# MPU.net
KiCad netlist of a schematic drawn in EAGLE
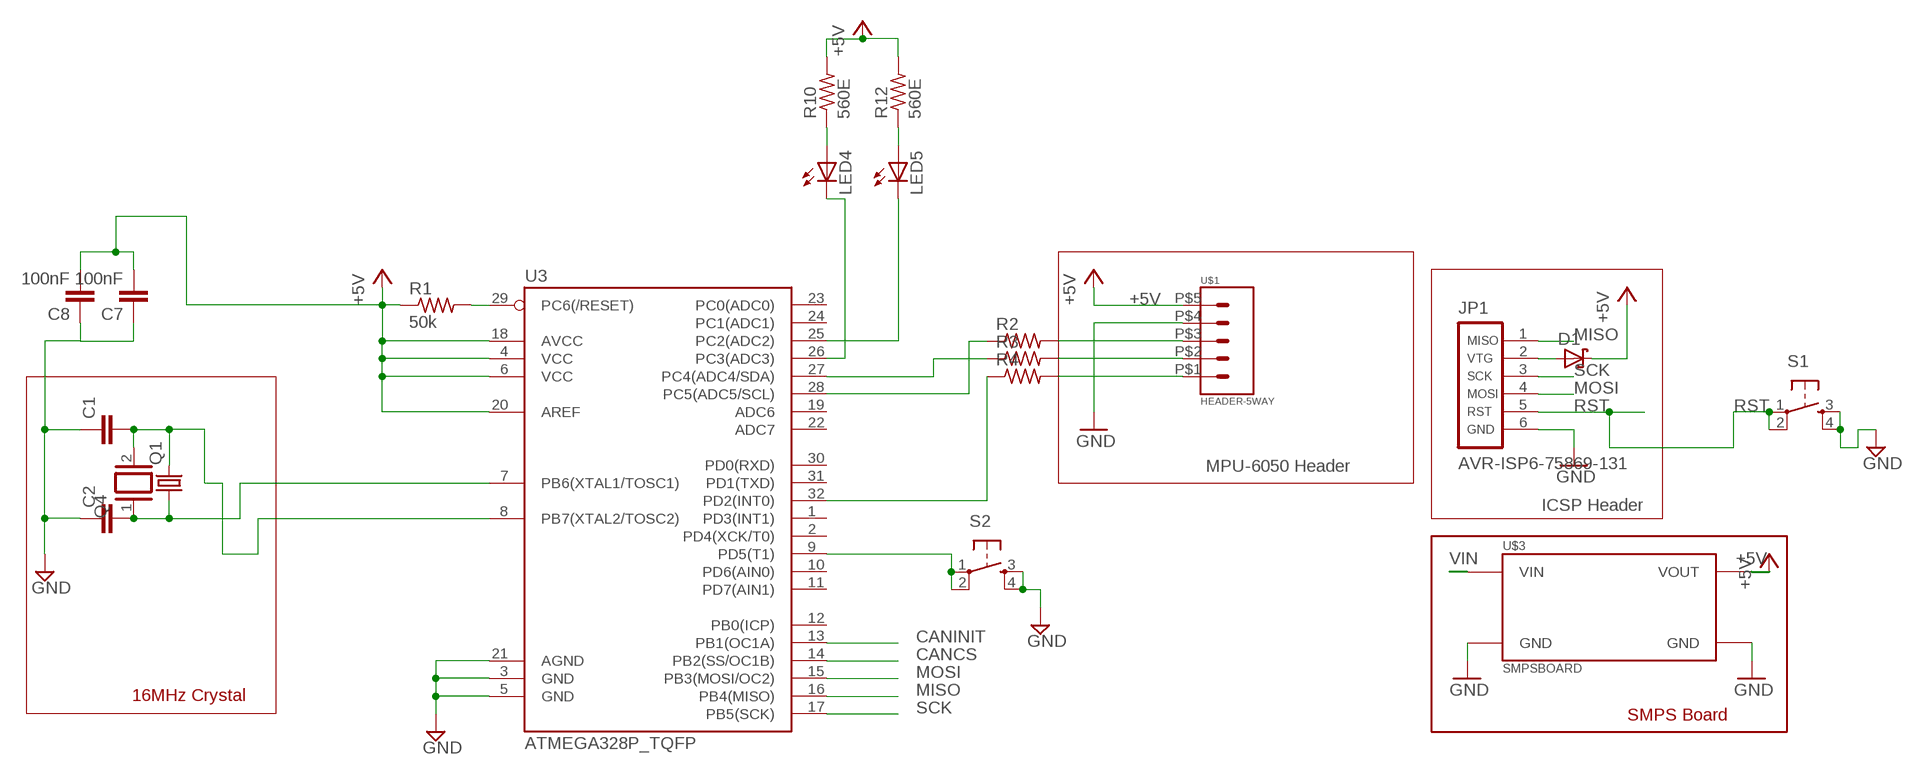
[diagram p0: schematic, sheet 1]
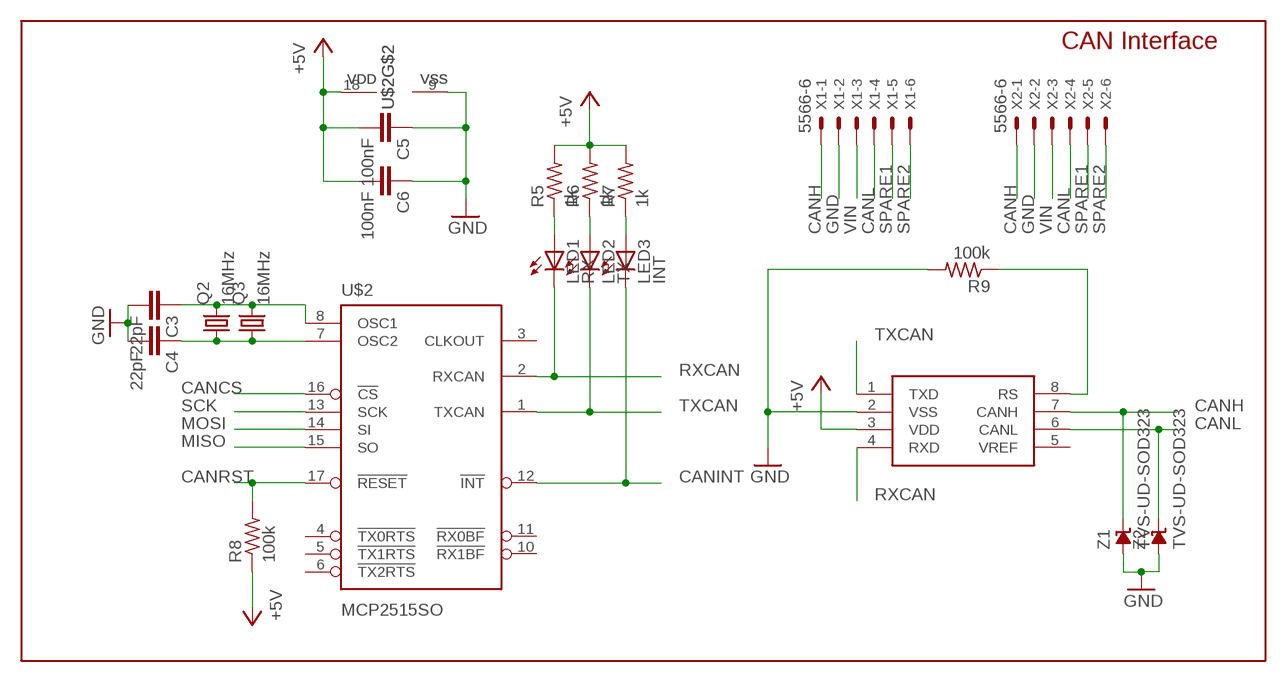
[diagram p1: schematic, sheet 2]

(export (version "E")
  (design (tool "Eeschema 10.0.6"))
  (components
    (comp (ref "C3")
      (value "22pF")
      (footprint "eagle-import:C0805K")
      (libsource (lib "eagle-import") (part "C-EUC0805K"))
    )
    (comp (ref "C4")
      (value "22pF")
      (footprint "eagle-import:C0805K")
      (libsource (lib "eagle-import") (part "C-EUC0805K"))
    )
    (comp (ref "C5")
      (value "100nF")
      (footprint "eagle-import:C0805K")
      (libsource (lib "eagle-import") (part "C-EUC0805K"))
    )
    (comp (ref "C6")
      (value "100nF")
      (footprint "eagle-import:C0805K")
      (libsource (lib "eagle-import") (part "C-EUC0805K"))
    )
    (comp (ref "LED1")
      (value "RX")
      (footprint "eagle-import:CHIP-LED0805")
      (libsource (lib "eagle-import") (part "LEDCHIP-LED0805"))
    )
    (comp (ref "LED2")
      (value "TX")
      (footprint "eagle-import:CHIP-LED0805")
      (libsource (lib "eagle-import") (part "LEDCHIP-LED0805"))
    )
    (comp (ref "LED3")
      (value "INT")
      (footprint "eagle-import:CHIP-LED0805")
      (libsource (lib "eagle-import") (part "LEDCHIP-LED0805"))
    )
    (comp (ref "Q2")
      (value "16MHz")
      (footprint "eagle-import:HC49_S")
      (libsource (lib "eagle-import") (part "CRYSTALHC49S"))
    )
    (comp (ref "Q3")
      (value "16MHz")
      (footprint "eagle-import:HC49UP")
      (libsource (lib "eagle-import") (part "CRYSTALHC49UP"))
    )
    (comp (ref "R5")
      (value "1k")
      (footprint "eagle-import:R0805")
      (libsource (lib "eagle-import") (part "R-US_R0805"))
    )
    (comp (ref "R6")
      (value "1k")
      (footprint "eagle-import:R0805")
      (libsource (lib "eagle-import") (part "R-US_R0805"))
    )
    (comp (ref "R7")
      (value "1k")
      (footprint "eagle-import:R0805")
      (libsource (lib "eagle-import") (part "R-US_R0805"))
    )
    (comp (ref "R8")
      (value "100k")
      (footprint "eagle-import:R0805")
      (libsource (lib "eagle-import") (part "R-US_R0805"))
    )
    (comp (ref "R9")
      (value "100k")
      (footprint "eagle-import:R0805")
      (libsource (lib "eagle-import") (part "R-US_R0805"))
    )
    (comp (ref "U$2")
      (value "MCP2515SO")
      (footprint "eagle-import:SO-18W")
      (libsource (lib "eagle-import") (part "MCP2515SO"))
    )
    (comp (ref "U2")
      (value "MCP2551")
      (footprint "eagle-import:SO08")
      (libsource (lib "eagle-import") (part "MCP2551"))
    )
    (comp (ref "X1")
      (value "5566-6")
      (footprint "eagle-import:5566-6")
      (fields (field (name "MPN") "95566-61002"))
      (libsource (lib "eagle-import") (part "5566-6"))
    )
    (comp (ref "X2")
      (value "5566-6")
      (footprint "eagle-import:5566-6")
      (fields (field (name "MPN") "95566-61002"))
      (libsource (lib "eagle-import") (part "5566-6"))
    )
    (comp (ref "Z1")
      (value "TVS-UD-SOD323")
      (footprint "eagle-import:SOD323")
      (libsource (lib "eagle-import") (part "TVS-UD-SOD323"))
    )
    (comp (ref "Z2")
      (value "TVS-UD-SOD323")
      (footprint "eagle-import:SOD323")
      (libsource (lib "eagle-import") (part "TVS-UD-SOD323"))
    )
    (comp (ref "C1")
      (value "C-EUC0805")
      (footprint "eagle-import:C0805")
      (libsource (lib "eagle-import") (part "C-EUC0805"))
    )
    (comp (ref "C2")
      (value "C-EUC0805")
      (footprint "eagle-import:C0805")
      (libsource (lib "eagle-import") (part "C-EUC0805"))
    )
    (comp (ref "C7")
      (value "100nF")
      (footprint "eagle-import:C0805")
      (libsource (lib "eagle-import") (part "C-EUC0805"))
    )
    (comp (ref "C8")
      (value "100nF")
      (footprint "eagle-import:C0805")
      (libsource (lib "eagle-import") (part "C-EUC0805"))
    )
    (comp (ref "D1")
      (value "SCHOTTKY-DIODESMD")
      (footprint "eagle-import:SMB")
      (libsource (lib "eagle-import") (part "SCHOTTKY-DIODESMD"))
    )
    (comp (ref "JP1")
      (value "AVR-ISP6-75869-131")
      (footprint "eagle-import:HDR-75869-131")
      (libsource (lib "eagle-import") (part "AVR-ISP6-75869-131"))
    )
    (comp (ref "LED4")
      (value "LEDCHIP-LED0805")
      (footprint "eagle-import:CHIP-LED0805")
      (libsource (lib "eagle-import") (part "LEDCHIP-LED0805"))
    )
    (comp (ref "LED5")
      (value "LEDCHIP-LED0805")
      (footprint "eagle-import:CHIP-LED0805")
      (libsource (lib "eagle-import") (part "LEDCHIP-LED0805"))
    )
    (comp (ref "Q1")
      (value "CRYSTALHC49UP")
      (footprint "eagle-import:HC49UP")
      (libsource (lib "eagle-import") (part "CRYSTALHC49UP"))
    )
    (comp (ref "Q4")
      (value "XTAL/S")
      (footprint "eagle-import:QS")
      (libsource (lib "eagle-import") (part "XTAL/S"))
    )
    (comp (ref "R1")
      (value "50k")
      (footprint "eagle-import:M0805")
      (libsource (lib "eagle-import") (part "R-US_M0805"))
    )
    (comp (ref "R2")
      (value "R-US_M0805")
      (footprint "eagle-import:M0805")
      (libsource (lib "eagle-import") (part "R-US_M0805"))
    )
    (comp (ref "R3")
      (value "R-US_M0805")
      (footprint "eagle-import:M0805")
      (libsource (lib "eagle-import") (part "R-US_M0805"))
    )
    (comp (ref "R4")
      (value "R-US_M0805")
      (footprint "eagle-import:M0805")
      (libsource (lib "eagle-import") (part "R-US_M0805"))
    )
    (comp (ref "R10")
      (value "560E")
      (footprint "eagle-import:M0805")
      (libsource (lib "eagle-import") (part "R-US_M0805"))
    )
    (comp (ref "R12")
      (value "560E")
      (footprint "eagle-import:M0805")
      (libsource (lib "eagle-import") (part "R-US_M0805"))
    )
    (comp (ref "S1")
      (value "TAC_SWITCHSMD")
      (footprint "eagle-import:TACTILE_SWITCH_SMD")
      (libsource (lib "eagle-import") (part "TAC_SWITCHSMD"))
    )
    (comp (ref "S2")
      (value "TAC_SWITCHSMD")
      (footprint "eagle-import:TACTILE_SWITCH_SMD")
      (libsource (lib "eagle-import") (part "TAC_SWITCHSMD"))
    )
    (comp (ref "U$1")
      (value "HEADER-5WAY")
      (footprint "eagle-import:1744426-5")
      (libsource (lib "eagle-import") (part "HEADER-5WAY"))
    )
    (comp (ref "U$3")
      (value "SMPSBOARD")
      (footprint "eagle-import:SMPSBOARD")
      (libsource (lib "eagle-import") (part "SMPSBOARD"))
    )
    (comp (ref "U3")
      (value "ATMEGA328P_TQFP")
      (footprint "eagle-import:TQFP32-08")
      (libsource (lib "eagle-import") (part "ATMEGA328P_TQFP"))
    )
  )
  (nets
    (net (code "1") (name "+5V") (class "Default")
      (node (ref "C5") (pin "2") (pinfunction "2_2") (pintype "passive"))
      (node (ref "C6") (pin "2") (pinfunction "2_2") (pintype "passive"))
      (node (ref "C7") (pin "2") (pinfunction "2_2") (pintype "passive"))
      (node (ref "C8") (pin "2") (pinfunction "2_2") (pintype "passive"))
      (node (ref "D1") (pin "C") (pinfunction "C_C") (pintype "passive"))
      (node (ref "R1") (pin "1") (pinfunction "1_1") (pintype "passive"))
      (node (ref "R10") (pin "2") (pinfunction "2_2") (pintype "passive"))
      (node (ref "R12") (pin "2") (pinfunction "2_2") (pintype "passive"))
      (node (ref "R5") (pin "2") (pinfunction "2_2") (pintype "passive"))
      (node (ref "R6") (pin "2") (pinfunction "2_2") (pintype "passive"))
      (node (ref "R7") (pin "2") (pinfunction "2_2") (pintype "passive"))
      (node (ref "R8") (pin "1") (pinfunction "1_1") (pintype "passive"))
      (node (ref "U$1") (pin "P$5") (pinfunction "P$5_P$5") (pintype "passive"))
      (node (ref "U$2") (pin "18") (pinfunction "VDD_18") (pintype "power_in"))
      (node (ref "U$3") (pin "VOUT") (pinfunction "VOUT_VOUT") (pintype "bidirectional"))
      (node (ref "U2") (pin "3") (pinfunction "VDD_3") (pintype "bidirectional"))
      (node (ref "U3") (pin "18") (pinfunction "AVCC_18") (pintype "bidirectional"))
      (node (ref "U3") (pin "20") (pinfunction "AREF_20") (pintype "bidirectional"))
      (node (ref "U3") (pin "4") (pinfunction "VCC_4") (pintype "bidirectional"))
      (node (ref "U3") (pin "6") (pinfunction "VCC_6") (pintype "bidirectional"))
    )
    (net (code "2") (name "CANCS") (class "Default")
      (node (ref "U$2") (pin "16") (pinfunction "~{CS}_16") (pintype "input"))
      (node (ref "U3") (pin "14") (pinfunction "PB2(SS/OC1B)_14") (pintype "bidirectional"))
    )
    (net (code "3") (name "CANH") (class "Default")
      (node (ref "U2") (pin "7") (pinfunction "CANH_7") (pintype "bidirectional"))
      (node (ref "X1") (pin "1") (pinfunction "S_1") (pintype "passive"))
      (node (ref "X2") (pin "1") (pinfunction "S_1") (pintype "passive"))
      (node (ref "Z1") (pin "C") (pinfunction "C_C") (pintype "passive"))
    )
    (net (code "4") (name "CANINIT") (class "Default")
      (node (ref "U3") (pin "13") (pinfunction "PB1(OC1A)_13") (pintype "bidirectional"))
    )
    (net (code "5") (name "CANINT") (class "Default")
      (node (ref "LED3") (pin "C") (pinfunction "C_C") (pintype "passive"))
      (node (ref "U$2") (pin "12") (pinfunction "~{INT}_12") (pintype "output"))
    )
    (net (code "6") (name "CANL") (class "Default")
      (node (ref "U2") (pin "6") (pinfunction "CANL_6") (pintype "bidirectional"))
      (node (ref "X1") (pin "4") (pinfunction "S_4") (pintype "passive"))
      (node (ref "X2") (pin "4") (pinfunction "S_4") (pintype "passive"))
      (node (ref "Z2") (pin "C") (pinfunction "C_C") (pintype "passive"))
    )
    (net (code "7") (name "CANRST") (class "Default")
      (node (ref "R8") (pin "2") (pinfunction "2_2") (pintype "passive"))
      (node (ref "U$2") (pin "17") (pinfunction "~{RESET}_17") (pintype "input"))
    )
    (net (code "8") (name "GND") (class "Default")
      (node (ref "C1") (pin "1") (pinfunction "1_1") (pintype "passive"))
      (node (ref "C2") (pin "1") (pinfunction "1_1") (pintype "passive"))
      (node (ref "C3") (pin "2") (pinfunction "2_2") (pintype "passive"))
      (node (ref "C4") (pin "2") (pinfunction "2_2") (pintype "passive"))
      (node (ref "C5") (pin "1") (pinfunction "1_1") (pintype "passive"))
      (node (ref "C6") (pin "1") (pinfunction "1_1") (pintype "passive"))
      (node (ref "C7") (pin "1") (pinfunction "1_1") (pintype "passive"))
      (node (ref "C8") (pin "1") (pinfunction "1_1") (pintype "passive"))
      (node (ref "JP1") (pin "6") (pinfunction "6_6") (pintype "passive"))
      (node (ref "R9") (pin "2") (pinfunction "2_2") (pintype "passive"))
      (node (ref "S1") (pin "3") (pinfunction "3_3") (pintype "passive"))
      (node (ref "S1") (pin "4") (pinfunction "4_4") (pintype "passive"))
      (node (ref "S2") (pin "3") (pinfunction "3_3") (pintype "passive"))
      (node (ref "S2") (pin "4") (pinfunction "4_4") (pintype "passive"))
      (node (ref "U$1") (pin "P$4") (pinfunction "P$4_P$4") (pintype "passive"))
      (node (ref "U$2") (pin "9") (pinfunction "VSS_9") (pintype "power_in"))
      (node (ref "U$3") (pin "GND") (pinfunction "GND_GND") (pintype "bidirectional"))
      (node (ref "U$3") (pin "GND@") (pinfunction "GND_GND@") (pintype "bidirectional"))
      (node (ref "U2") (pin "2") (pinfunction "VSS_2") (pintype "bidirectional"))
      (node (ref "U3") (pin "21") (pinfunction "AGND_21") (pintype "bidirectional"))
      (node (ref "U3") (pin "3") (pinfunction "GND_3") (pintype "bidirectional"))
      (node (ref "U3") (pin "5") (pinfunction "GND_5") (pintype "bidirectional"))
      (node (ref "X1") (pin "2") (pinfunction "S_2") (pintype "passive"))
      (node (ref "X2") (pin "2") (pinfunction "S_2") (pintype "passive"))
      (node (ref "Z1") (pin "A") (pinfunction "A_A") (pintype "passive"))
      (node (ref "Z2") (pin "A") (pinfunction "A_A") (pintype "passive"))
    )
    (net (code "9") (name "MISO") (class "Default")
      (node (ref "JP1") (pin "1") (pinfunction "1_1") (pintype "passive"))
      (node (ref "U$2") (pin "15") (pinfunction "SO_15") (pintype "output"))
      (node (ref "U3") (pin "16") (pinfunction "PB4(MISO)_16") (pintype "bidirectional"))
    )
    (net (code "10") (name "MOSI") (class "Default")
      (node (ref "JP1") (pin "4") (pinfunction "4_4") (pintype "passive"))
      (node (ref "U$2") (pin "14") (pinfunction "SI_14") (pintype "input"))
      (node (ref "U3") (pin "15") (pinfunction "PB3(MOSI/OC2)_15") (pintype "bidirectional"))
    )
    (net (code "11") (name "Net-(D1-PadA)") (class "Default")
      (node (ref "D1") (pin "A") (pinfunction "A_A") (pintype "passive"))
      (node (ref "JP1") (pin "2") (pinfunction "2_2") (pintype "passive"))
    )
    (net (code "12") (name "Net-(LED1-PadA)") (class "Default")
      (node (ref "LED1") (pin "A") (pinfunction "A_A") (pintype "passive"))
      (node (ref "R5") (pin "1") (pinfunction "1_1") (pintype "passive"))
    )
    (net (code "13") (name "Net-(LED2-PadA)") (class "Default")
      (node (ref "LED2") (pin "A") (pinfunction "A_A") (pintype "passive"))
      (node (ref "R6") (pin "1") (pinfunction "1_1") (pintype "passive"))
    )
    (net (code "14") (name "Net-(LED3-PadA)") (class "Default")
      (node (ref "LED3") (pin "A") (pinfunction "A_A") (pintype "passive"))
      (node (ref "R7") (pin "1") (pinfunction "1_1") (pintype "passive"))
    )
    (net (code "15") (name "Net-(LED4-PadA)") (class "Default")
      (node (ref "LED4") (pin "A") (pinfunction "A_A") (pintype "passive"))
      (node (ref "R10") (pin "1") (pinfunction "1_1") (pintype "passive"))
    )
    (net (code "16") (name "Net-(LED5-PadA)") (class "Default")
      (node (ref "LED5") (pin "A") (pinfunction "A_A") (pintype "passive"))
      (node (ref "R12") (pin "1") (pinfunction "1_1") (pintype "passive"))
    )
    (net (code "17") (name "Net-(R2-Pad2)") (class "Default")
      (node (ref "R2") (pin "2") (pinfunction "2_2") (pintype "passive"))
      (node (ref "U$1") (pin "P$3") (pinfunction "P$3_P$3") (pintype "passive"))
    )
    (net (code "18") (name "Net-(R3-Pad2)") (class "Default")
      (node (ref "R3") (pin "2") (pinfunction "2_2") (pintype "passive"))
      (node (ref "U$1") (pin "P$2") (pinfunction "P$2_P$2") (pintype "passive"))
    )
    (net (code "19") (name "Net-(R4-Pad2)") (class "Default")
      (node (ref "R4") (pin "2") (pinfunction "2_2") (pintype "passive"))
      (node (ref "U$1") (pin "P$1") (pinfunction "P$1_P$1") (pintype "passive"))
    )
    (net (code "20") (name "Net-(U$2A-OSC1)") (class "Default")
      (node (ref "C3") (pin "1") (pinfunction "1_1") (pintype "passive"))
      (node (ref "Q2") (pin "2") (pinfunction "2_2") (pintype "passive"))
      (node (ref "Q3") (pin "2") (pinfunction "2_2") (pintype "passive"))
      (node (ref "U$2") (pin "8") (pinfunction "OSC1_8") (pintype "input"))
    )
    (net (code "21") (name "Net-(U$2A-OSC2)") (class "Default")
      (node (ref "C4") (pin "1") (pinfunction "1_1") (pintype "passive"))
      (node (ref "Q2") (pin "1") (pinfunction "1_1") (pintype "passive"))
      (node (ref "Q3") (pin "1") (pinfunction "1_1") (pintype "passive"))
      (node (ref "U$2") (pin "7") (pinfunction "OSC2_7") (pintype "output"))
    )
    (net (code "22") (name "Net-(U2-RS)") (class "Default")
      (node (ref "R9") (pin "1") (pinfunction "1_1") (pintype "passive"))
      (node (ref "U2") (pin "8") (pinfunction "RS_8") (pintype "bidirectional"))
    )
    (net (code "23") (name "Net-(U3-PB6(XTAL1{slash}TOSC1))") (class "Default")
      (node (ref "C2") (pin "2") (pinfunction "2_2") (pintype "passive"))
      (node (ref "Q1") (pin "1") (pinfunction "1_1") (pintype "passive"))
      (node (ref "Q4") (pin "1") (pinfunction "1_1") (pintype "passive"))
      (node (ref "U3") (pin "7") (pinfunction "PB6(XTAL1/TOSC1)_7") (pintype "bidirectional"))
    )
    (net (code "24") (name "Net-(U3-PB7(XTAL2{slash}TOSC2))") (class "Default")
      (node (ref "C1") (pin "2") (pinfunction "2_2") (pintype "passive"))
      (node (ref "Q1") (pin "2") (pinfunction "2_2") (pintype "passive"))
      (node (ref "Q4") (pin "2") (pinfunction "2_2") (pintype "passive"))
      (node (ref "U3") (pin "8") (pinfunction "PB7(XTAL2/TOSC2)_8") (pintype "bidirectional"))
    )
    (net (code "25") (name "Net-(U3-PC2(ADC2))") (class "Default")
      (node (ref "LED5") (pin "C") (pinfunction "C_C") (pintype "passive"))
      (node (ref "U3") (pin "25") (pinfunction "PC2(ADC2)_25") (pintype "bidirectional"))
    )
    (net (code "26") (name "Net-(U3-PC3(ADC3))") (class "Default")
      (node (ref "LED4") (pin "C") (pinfunction "C_C") (pintype "passive"))
      (node (ref "U3") (pin "26") (pinfunction "PC3(ADC3)_26") (pintype "bidirectional"))
    )
    (net (code "27") (name "Net-(U3-PC4(ADC4{slash}SDA))") (class "Default")
      (node (ref "R3") (pin "1") (pinfunction "1_1") (pintype "passive"))
      (node (ref "U3") (pin "27") (pinfunction "PC4(ADC4/SDA)_27") (pintype "bidirectional"))
    )
    (net (code "28") (name "Net-(U3-PC5(ADC5{slash}SCL))") (class "Default")
      (node (ref "R2") (pin "1") (pinfunction "1_1") (pintype "passive"))
      (node (ref "U3") (pin "28") (pinfunction "PC5(ADC5/SCL)_28") (pintype "bidirectional"))
    )
    (net (code "29") (name "Net-(U3-PC6({slash}RESET))") (class "Default")
      (node (ref "R1") (pin "2") (pinfunction "2_2") (pintype "passive"))
      (node (ref "U3") (pin "29") (pinfunction "PC6(/RESET)_29") (pintype "bidirectional"))
    )
    (net (code "30") (name "Net-(U3-PD2(INT0))") (class "Default")
      (node (ref "R4") (pin "1") (pinfunction "1_1") (pintype "passive"))
      (node (ref "U3") (pin "32") (pinfunction "PD2(INT0)_32") (pintype "bidirectional"))
    )
    (net (code "31") (name "Net-(U3-PD5(T1))") (class "Default")
      (node (ref "S2") (pin "1") (pinfunction "1_1") (pintype "passive"))
      (node (ref "S2") (pin "2") (pinfunction "2_2") (pintype "passive"))
      (node (ref "U3") (pin "9") (pinfunction "PD5(T1)_9") (pintype "bidirectional"))
    )
    (net (code "32") (name "RST") (class "Default")
      (node (ref "JP1") (pin "5") (pinfunction "5_5") (pintype "passive"))
      (node (ref "S1") (pin "1") (pinfunction "1_1") (pintype "passive"))
      (node (ref "S1") (pin "2") (pinfunction "2_2") (pintype "passive"))
    )
    (net (code "33") (name "RXCAN") (class "Default")
      (node (ref "LED1") (pin "C") (pinfunction "C_C") (pintype "passive"))
      (node (ref "U$2") (pin "2") (pinfunction "RXCAN_2") (pintype "input"))
      (node (ref "U2") (pin "4") (pinfunction "RXD_4") (pintype "bidirectional"))
    )
    (net (code "34") (name "SCK") (class "Default")
      (node (ref "JP1") (pin "3") (pinfunction "3_3") (pintype "passive"))
      (node (ref "U$2") (pin "13") (pinfunction "SCK_13") (pintype "input"))
      (node (ref "U3") (pin "17") (pinfunction "PB5(SCK)_17") (pintype "bidirectional"))
    )
    (net (code "35") (name "SPARE1") (class "Default")
      (node (ref "X1") (pin "5") (pinfunction "S_5") (pintype "passive"))
      (node (ref "X2") (pin "5") (pinfunction "S_5") (pintype "passive"))
    )
    (net (code "36") (name "SPARE2") (class "Default")
      (node (ref "X1") (pin "6") (pinfunction "S_6") (pintype "passive"))
      (node (ref "X2") (pin "6") (pinfunction "S_6") (pintype "passive"))
    )
    (net (code "37") (name "TXCAN") (class "Default")
      (node (ref "LED2") (pin "C") (pinfunction "C_C") (pintype "passive"))
      (node (ref "U$2") (pin "1") (pinfunction "TXCAN_1") (pintype "output"))
      (node (ref "U2") (pin "1") (pinfunction "TXD_1") (pintype "bidirectional"))
    )
    (net (code "38") (name "VIN") (class "Default")
      (node (ref "U$3") (pin "VIN") (pinfunction "VIN_VIN") (pintype "bidirectional"))
      (node (ref "X1") (pin "3") (pinfunction "S_3") (pintype "passive"))
      (node (ref "X2") (pin "3") (pinfunction "S_3") (pintype "passive"))
    )
    (net (code "39") (name "unconnected-(U$2A-CLKOUT-Pad3)") (class "Default")
      (node (ref "U$2") (pin "3") (pinfunction "CLKOUT_3") (pintype "output"))
    )
    (net (code "40") (name "unconnected-(U$2A-~{RX0BF}-Pad11)") (class "Default")
      (node (ref "U$2") (pin "11") (pinfunction "~{RX0BF}_11") (pintype "output"))
    )
    (net (code "41") (name "unconnected-(U$2A-~{RX1BF}-Pad10)") (class "Default")
      (node (ref "U$2") (pin "10") (pinfunction "~{RX1BF}_10") (pintype "output"))
    )
    (net (code "42") (name "unconnected-(U$2A-~{TX0RTS}-Pad4)") (class "Default")
      (node (ref "U$2") (pin "4") (pinfunction "~{TX0RTS}_4") (pintype "input"))
    )
    (net (code "43") (name "unconnected-(U$2A-~{TX1RTS}-Pad5)") (class "Default")
      (node (ref "U$2") (pin "5") (pinfunction "~{TX1RTS}_5") (pintype "input"))
    )
    (net (code "44") (name "unconnected-(U$2A-~{TX2RTS}-Pad6)") (class "Default")
      (node (ref "U$2") (pin "6") (pinfunction "~{TX2RTS}_6") (pintype "input"))
    )
    (net (code "45") (name "unconnected-(U2-VREF-Pad5)") (class "Default")
      (node (ref "U2") (pin "5") (pinfunction "VREF_5") (pintype "bidirectional"))
    )
    (net (code "46") (name "unconnected-(U3-ADC6-Pad19)") (class "Default")
      (node (ref "U3") (pin "19") (pinfunction "ADC6_19") (pintype "bidirectional"))
    )
    (net (code "47") (name "unconnected-(U3-ADC7-Pad22)") (class "Default")
      (node (ref "U3") (pin "22") (pinfunction "ADC7_22") (pintype "bidirectional"))
    )
    (net (code "48") (name "unconnected-(U3-PB0(ICP)-Pad12)") (class "Default")
      (node (ref "U3") (pin "12") (pinfunction "PB0(ICP)_12") (pintype "bidirectional"))
    )
    (net (code "49") (name "unconnected-(U3-PC0(ADC0)-Pad23)") (class "Default")
      (node (ref "U3") (pin "23") (pinfunction "PC0(ADC0)_23") (pintype "bidirectional"))
    )
    (net (code "50") (name "unconnected-(U3-PC1(ADC1)-Pad24)") (class "Default")
      (node (ref "U3") (pin "24") (pinfunction "PC1(ADC1)_24") (pintype "bidirectional"))
    )
    (net (code "51") (name "unconnected-(U3-PD0(RXD)-Pad30)") (class "Default")
      (node (ref "U3") (pin "30") (pinfunction "PD0(RXD)_30") (pintype "bidirectional"))
    )
    (net (code "52") (name "unconnected-(U3-PD1(TXD)-Pad31)") (class "Default")
      (node (ref "U3") (pin "31") (pinfunction "PD1(TXD)_31") (pintype "bidirectional"))
    )
    (net (code "53") (name "unconnected-(U3-PD3(INT1)-Pad1)") (class "Default")
      (node (ref "U3") (pin "1") (pinfunction "PD3(INT1)_1") (pintype "bidirectional"))
    )
    (net (code "54") (name "unconnected-(U3-PD4(XCK{slash}T0)-Pad2)") (class "Default")
      (node (ref "U3") (pin "2") (pinfunction "PD4(XCK/T0)_2") (pintype "bidirectional"))
    )
    (net (code "55") (name "unconnected-(U3-PD6(AIN0)-Pad10)") (class "Default")
      (node (ref "U3") (pin "10") (pinfunction "PD6(AIN0)_10") (pintype "bidirectional"))
    )
    (net (code "56") (name "unconnected-(U3-PD7(AIN1)-Pad11)") (class "Default")
      (node (ref "U3") (pin "11") (pinfunction "PD7(AIN1)_11") (pintype "bidirectional"))
    )
  )
)
